# LipSync_Switch_Board.net
KiCad netlist of a schematic drawn in EAGLE
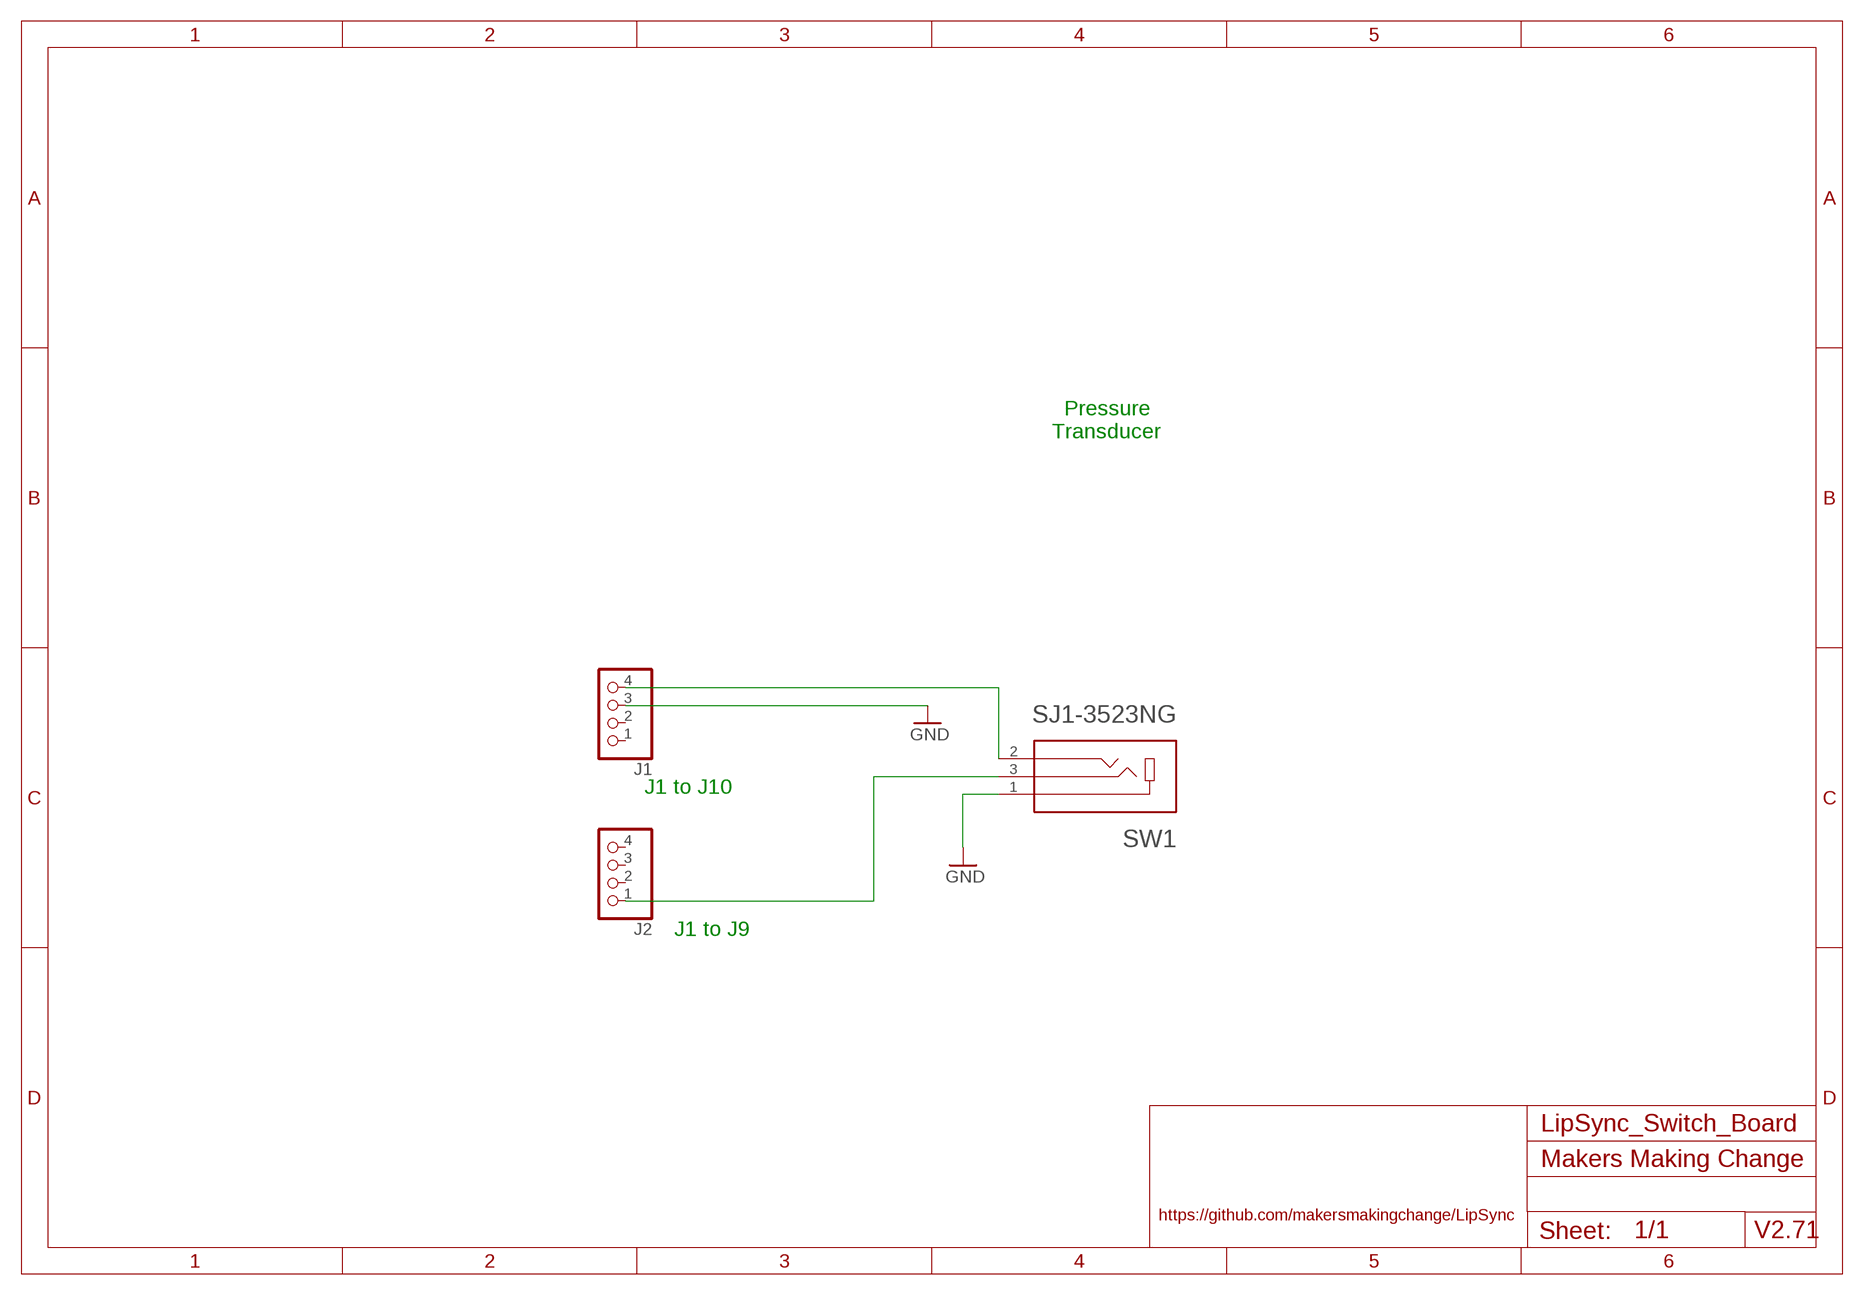
[diagram p0: schematic, sheet 1]

(export (version "E")
  (design (tool "Eeschema 10.0.6"))
  (components
    (comp (ref "J1")
      (value "PINHEAD_PINHD-1X4")
      (footprint "eagle-import:PINHEAD_1X04")
      (libsource (lib "eagle-import") (part "PINHEAD_PINHD-1X4"))
    )
    (comp (ref "J2")
      (value "PINHEAD_PINHD-1X4")
      (footprint "eagle-import:PINHEAD_1X04")
      (libsource (lib "eagle-import") (part "PINHEAD_PINHD-1X4"))
    )
    (comp (ref "SW1")
      (value "SJ1-3523NG")
      (footprint "eagle-import:CUI_SJ1-3523NG")
      (fields (field (name "MANUFACTURER") "CUI"))
      (libsource (lib "eagle-import") (part "SJ1-3523NG"))
    )
  )
  (nets
    (net (code "1") (name "GND") (class "Default")
      (node (ref "J1") (pin "3") (pinfunction "3_3") (pintype "passive"))
      (node (ref "SW1") (pin "1") (pinfunction "1_1") (pintype "passive"))
    )
    (net (code "2") (name "Net-(J1-Pad4)") (class "Default")
      (node (ref "J1") (pin "4") (pinfunction "4_4") (pintype "passive"))
      (node (ref "SW1") (pin "2") (pinfunction "2_2") (pintype "passive"))
    )
    (net (code "3") (name "Net-(J2-Pad1)") (class "Default")
      (node (ref "J2") (pin "1") (pinfunction "1_1") (pintype "passive"))
      (node (ref "SW1") (pin "3") (pinfunction "3_3") (pintype "passive"))
    )
    (net (code "4") (name "unconnected-(J1-Pad1)") (class "Default")
      (node (ref "J1") (pin "1") (pinfunction "1_1") (pintype "passive"))
    )
    (net (code "5") (name "unconnected-(J1-Pad2)") (class "Default")
      (node (ref "J1") (pin "2") (pinfunction "2_2") (pintype "passive"))
    )
    (net (code "6") (name "unconnected-(J2-Pad2)") (class "Default")
      (node (ref "J2") (pin "2") (pinfunction "2_2") (pintype "passive"))
    )
    (net (code "7") (name "unconnected-(J2-Pad3)") (class "Default")
      (node (ref "J2") (pin "3") (pinfunction "3_3") (pintype "passive"))
    )
    (net (code "8") (name "unconnected-(J2-Pad4)") (class "Default")
      (node (ref "J2") (pin "4") (pinfunction "4_4") (pintype "passive"))
    )
  )
)
